# VDMEDA_Main.net
KiCad netlist of a schematic drawn in Altium Designer
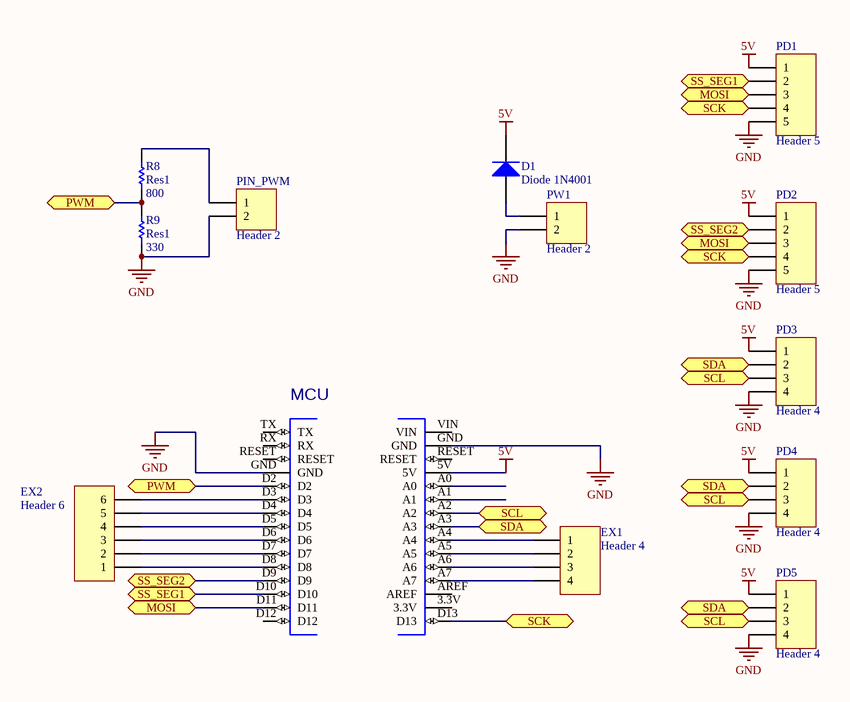
[diagram p0: VDMEDA_Main.SchDoc]

(export (version "E")
  (design (tool "Eeschema 10.0.6"))
  (components
    (comp (ref "D1")
      (value "Diode 1N4001")
      (footprint "DO-41")
      (description "1 Amp General Purpose Rectifier")
      (fields (field (name "PUBLISHER") "Altium Limited"))
      (libsource (lib "Miscellaneous Devices") (part "Diode 1N4001"))
    )
    (comp (ref "EX1")
      (value "Header 4")
      (footprint "HDR1X4")
      (description "Header, 4-Pin")
      (fields (field (name "PUBLISHER") "Altium Limited"))
      (libsource (lib "Miscellaneous Connectors") (part "Header 4"))
    )
    (comp (ref "EX2")
      (value "Header 6")
      (footprint "HDR1X6")
      (description "Header, 6-Pin")
      (fields (field (name "PUBLISHER") "Altium Limited"))
      (libsource (lib "Miscellaneous Connectors") (part "Header 6"))
    )
    (comp (ref "MCU")
      (value "ARDUINO_NANO")
      (footprint "ARDUINO_NANO_ARDUINO_NANO(Primary)")
      (libsource (lib "ARDUINO_NANO") (part "ARDUINO_NANO"))
    )
    (comp (ref "PD1")
      (value "Header 5")
      (footprint "HDR1X5")
      (description "Header, 5-Pin")
      (fields (field (name "PUBLISHER") "Altium Limited"))
      (libsource (lib "Miscellaneous Connectors") (part "Header 5"))
    )
    (comp (ref "PD2")
      (value "Header 5")
      (footprint "HDR1X5")
      (description "Header, 5-Pin")
      (fields (field (name "PUBLISHER") "Altium Limited"))
      (libsource (lib "Miscellaneous Connectors") (part "Header 5"))
    )
    (comp (ref "PD3")
      (value "Header 4")
      (footprint "HDR1X4")
      (description "Header, 4-Pin")
      (fields (field (name "PUBLISHER") "Altium Limited"))
      (libsource (lib "Miscellaneous Connectors") (part "Header 4"))
    )
    (comp (ref "PD4")
      (value "Header 4")
      (footprint "HDR1X4")
      (description "Header, 4-Pin")
      (fields (field (name "PUBLISHER") "Altium Limited"))
      (libsource (lib "Miscellaneous Connectors") (part "Header 4"))
    )
    (comp (ref "PD5")
      (value "Header 4")
      (footprint "HDR1X4")
      (description "Header, 4-Pin")
      (fields (field (name "PUBLISHER") "Altium Limited"))
      (libsource (lib "Miscellaneous Connectors") (part "Header 4"))
    )
    (comp (ref "PIN_PWM")
      (value "Header 2")
      (footprint "TO-220_A")
      (description "Header, 2-Pin")
      (fields (field (name "PUBLISHER") "Altium Limited"))
      (libsource (lib "Miscellaneous Connectors") (part "Header 2"))
    )
    (comp (ref "PW1")
      (value "Header 2")
      (footprint "TO-220_A")
      (description "Header, 2-Pin")
      (fields (field (name "PUBLISHER") "Altium Limited"))
      (libsource (lib "Miscellaneous Connectors") (part "Header 2"))
    )
    (comp (ref "R8")
      (value "Res1")
      (footprint "AXIAL-0.3")
      (description "Resistor")
      (fields (field (name "ALTIUM_VALUE") "800") (field (name "PUBLISHER") "Altium Limited"))
      (libsource (lib "Miscellaneous Devices") (part "Res1"))
    )
    (comp (ref "R9")
      (value "Res1")
      (footprint "AXIAL-0.3")
      (description "Resistor")
      (fields (field (name "ALTIUM_VALUE") "330") (field (name "PUBLISHER") "Altium Limited"))
      (libsource (lib "Miscellaneous Devices") (part "Res1"))
    )
  )
  (nets
    (net (code "1") (name "/MOSI") (class "Default")
      (node (ref "MCU") (pin "D11") (pinfunction "D11_D11") (pintype "bidirectional"))
      (node (ref "PD1") (pin "3") (pinfunction "3_3") (pintype "passive"))
      (node (ref "PD2") (pin "3") (pinfunction "3_3") (pintype "passive"))
    )
    (net (code "2") (name "/PWM") (class "Default")
      (node (ref "MCU") (pin "D2") (pinfunction "D2_D2") (pintype "bidirectional"))
      (node (ref "R8") (pin "1") (pinfunction "1_1") (pintype "passive"))
      (node (ref "R9") (pin "2") (pinfunction "2_2") (pintype "passive"))
    )
    (net (code "3") (name "/SCK") (class "Default")
      (node (ref "MCU") (pin "D13") (pinfunction "D13_D13") (pintype "bidirectional"))
      (node (ref "PD1") (pin "4") (pinfunction "4_4") (pintype "passive"))
      (node (ref "PD2") (pin "4") (pinfunction "4_4") (pintype "passive"))
    )
    (net (code "4") (name "/SCL") (class "Default")
      (node (ref "MCU") (pin "A2") (pinfunction "A2_A2") (pintype "bidirectional"))
      (node (ref "PD3") (pin "3") (pinfunction "3_3") (pintype "passive"))
      (node (ref "PD4") (pin "3") (pinfunction "3_3") (pintype "passive"))
      (node (ref "PD5") (pin "3") (pinfunction "3_3") (pintype "passive"))
    )
    (net (code "5") (name "/SDA") (class "Default")
      (node (ref "MCU") (pin "A3") (pinfunction "A3_A3") (pintype "bidirectional"))
      (node (ref "PD3") (pin "2") (pinfunction "2_2") (pintype "passive"))
      (node (ref "PD4") (pin "2") (pinfunction "2_2") (pintype "passive"))
      (node (ref "PD5") (pin "2") (pinfunction "2_2") (pintype "passive"))
    )
    (net (code "6") (name "/SS_SEG1") (class "Default")
      (node (ref "MCU") (pin "D10") (pinfunction "D10_D10") (pintype "bidirectional"))
      (node (ref "PD1") (pin "2") (pinfunction "2_2") (pintype "passive"))
    )
    (net (code "7") (name "/SS_SEG2") (class "Default")
      (node (ref "MCU") (pin "D9") (pinfunction "D9_D9") (pintype "bidirectional"))
      (node (ref "PD2") (pin "2") (pinfunction "2_2") (pintype "passive"))
    )
    (net (code "8") (name "5V") (class "Default")
      (node (ref "D1") (pin "2") (pinfunction "K_2") (pintype "passive"))
      (node (ref "MCU") (pin "5V") (pinfunction "5V_5V") (pintype "power_in"))
      (node (ref "PD1") (pin "1") (pinfunction "1_1") (pintype "passive"))
      (node (ref "PD2") (pin "1") (pinfunction "1_1") (pintype "passive"))
      (node (ref "PD3") (pin "1") (pinfunction "1_1") (pintype "passive"))
      (node (ref "PD4") (pin "1") (pinfunction "1_1") (pintype "passive"))
      (node (ref "PD5") (pin "1") (pinfunction "1_1") (pintype "passive"))
    )
    (net (code "9") (name "GND") (class "Default")
      (node (ref "MCU") (pin "GND") (pinfunction "GND_GND") (pintype "power_in"))
      (node (ref "PD1") (pin "5") (pinfunction "5_5") (pintype "passive"))
      (node (ref "PD2") (pin "5") (pinfunction "5_5") (pintype "passive"))
      (node (ref "PD3") (pin "4") (pinfunction "4_4") (pintype "passive"))
      (node (ref "PD4") (pin "4") (pinfunction "4_4") (pintype "passive"))
      (node (ref "PD5") (pin "4") (pinfunction "4_4") (pintype "passive"))
      (node (ref "PIN_PWM") (pin "2") (pinfunction "2_2") (pintype "passive"))
      (node (ref "PW1") (pin "2") (pinfunction "2_2") (pintype "passive"))
      (node (ref "R9") (pin "1") (pinfunction "1_1") (pintype "passive"))
    )
    (net (code "10") (name "Net-(D1-A)") (class "Default")
      (node (ref "D1") (pin "1") (pinfunction "A_1") (pintype "passive"))
      (node (ref "PW1") (pin "1") (pinfunction "1_1") (pintype "passive"))
    )
    (net (code "11") (name "Net-(EX1-Pad1)") (class "Default")
      (node (ref "EX1") (pin "1") (pinfunction "1_1") (pintype "passive"))
      (node (ref "MCU") (pin "A4") (pinfunction "A4_A4") (pintype "bidirectional"))
    )
    (net (code "12") (name "Net-(EX1-Pad2)") (class "Default")
      (node (ref "EX1") (pin "2") (pinfunction "2_2") (pintype "passive"))
      (node (ref "MCU") (pin "A5") (pinfunction "A5_A5") (pintype "bidirectional"))
    )
    (net (code "13") (name "Net-(EX1-Pad3)") (class "Default")
      (node (ref "EX1") (pin "3") (pinfunction "3_3") (pintype "passive"))
      (node (ref "MCU") (pin "A6") (pinfunction "A6_A6") (pintype "bidirectional"))
    )
    (net (code "14") (name "Net-(EX1-Pad4)") (class "Default")
      (node (ref "EX1") (pin "4") (pinfunction "4_4") (pintype "passive"))
      (node (ref "MCU") (pin "A7") (pinfunction "A7_A7") (pintype "bidirectional"))
    )
    (net (code "15") (name "Net-(EX2-Pad1)") (class "Default")
      (node (ref "EX2") (pin "1") (pinfunction "1_1") (pintype "passive"))
      (node (ref "MCU") (pin "D8") (pinfunction "D8_D8") (pintype "bidirectional"))
    )
    (net (code "16") (name "Net-(EX2-Pad2)") (class "Default")
      (node (ref "EX2") (pin "2") (pinfunction "2_2") (pintype "passive"))
      (node (ref "MCU") (pin "D7") (pinfunction "D7_D7") (pintype "bidirectional"))
    )
    (net (code "17") (name "Net-(EX2-Pad3)") (class "Default")
      (node (ref "EX2") (pin "3") (pinfunction "3_3") (pintype "passive"))
      (node (ref "MCU") (pin "D6") (pinfunction "D6_D6") (pintype "bidirectional"))
    )
    (net (code "18") (name "Net-(EX2-Pad4)") (class "Default")
      (node (ref "EX2") (pin "4") (pinfunction "4_4") (pintype "passive"))
      (node (ref "MCU") (pin "D5") (pinfunction "D5_D5") (pintype "bidirectional"))
    )
    (net (code "19") (name "Net-(EX2-Pad5)") (class "Default")
      (node (ref "EX2") (pin "5") (pinfunction "5_5") (pintype "passive"))
      (node (ref "MCU") (pin "D4") (pinfunction "D4_D4") (pintype "bidirectional"))
    )
    (net (code "20") (name "Net-(EX2-Pad6)") (class "Default")
      (node (ref "EX2") (pin "6") (pinfunction "6_6") (pintype "passive"))
      (node (ref "MCU") (pin "D3") (pinfunction "D3_D3") (pintype "bidirectional"))
    )
    (net (code "21") (name "Net-(PIN_PWM-Pad1)") (class "Default")
      (node (ref "PIN_PWM") (pin "1") (pinfunction "1_1") (pintype "passive"))
      (node (ref "R8") (pin "2") (pinfunction "2_2") (pintype "passive"))
    )
    (net (code "22") (name "unconnected-(MCU-Pad3.3V)") (class "Default")
      (node (ref "MCU") (pin "3.3V") (pinfunction "3.3V_3.3V") (pintype "power_in"))
    )
    (net (code "23") (name "unconnected-(MCU-PadA0)") (class "Default")
      (node (ref "MCU") (pin "A0") (pinfunction "A0_A0") (pintype "bidirectional"))
    )
    (net (code "24") (name "unconnected-(MCU-PadA1)") (class "Default")
      (node (ref "MCU") (pin "A1") (pinfunction "A1_A1") (pintype "bidirectional"))
    )
    (net (code "25") (name "unconnected-(MCU-PadAREF)") (class "Default")
      (node (ref "MCU") (pin "AREF") (pinfunction "AREF_AREF") (pintype "power_in"))
    )
    (net (code "26") (name "unconnected-(MCU-PadD12)") (class "Default")
      (node (ref "MCU") (pin "D12") (pinfunction "D12_D12") (pintype "bidirectional"))
    )
    (net (code "27") (name "unconnected-(MCU-PadRESET)") (class "Default")
      (node (ref "MCU") (pin "RESET") (pinfunction "RESET_RESET") (pintype "bidirectional"))
    )
    (net (code "28") (name "unconnected-(MCU-PadRESET)_1") (class "Default")
      (node (ref "MCU") (pin "RESET") (pinfunction "RESET_RESET") (pintype "bidirectional"))
    )
    (net (code "29") (name "unconnected-(MCU-PadRX)") (class "Default")
      (node (ref "MCU") (pin "RX") (pinfunction "RX_RX") (pintype "bidirectional"))
    )
    (net (code "30") (name "unconnected-(MCU-PadTX)") (class "Default")
      (node (ref "MCU") (pin "TX") (pinfunction "TX_TX") (pintype "bidirectional"))
    )
    (net (code "31") (name "unconnected-(MCU-PadVIN)") (class "Default")
      (node (ref "MCU") (pin "VIN") (pinfunction "VIN_VIN") (pintype "power_in"))
    )
  )
)
